# M8340X2.net
KiCad netlist of a schematic drawn in EAGLE
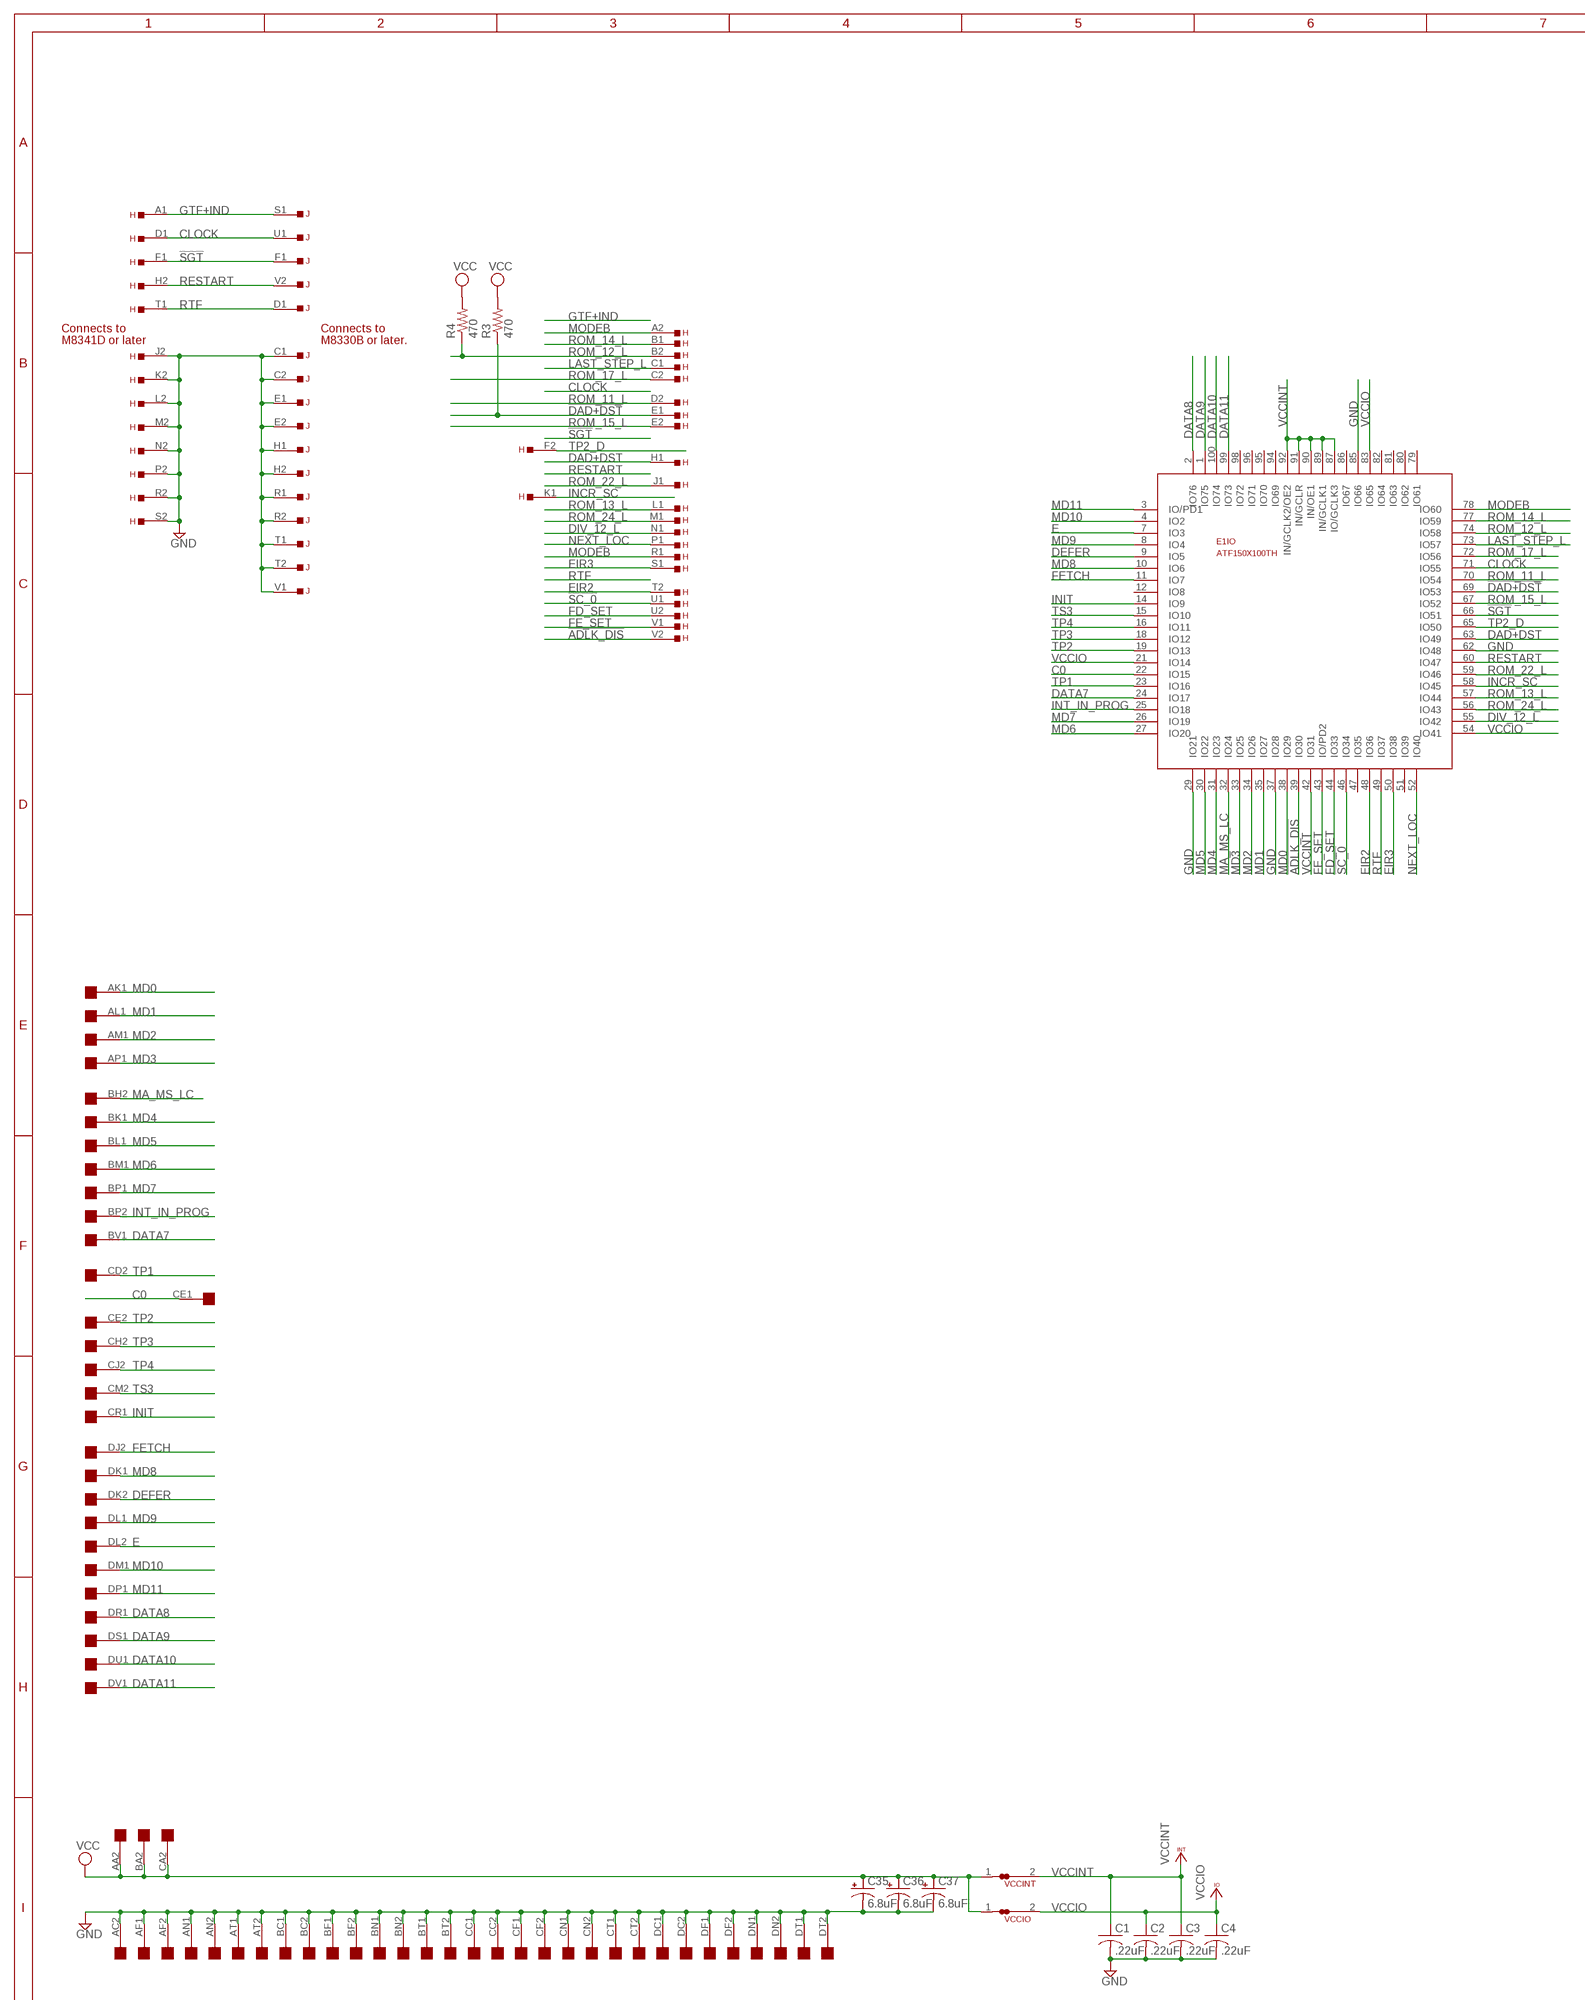
[diagram p0: schematic, sheet 1, part 1 of 2]
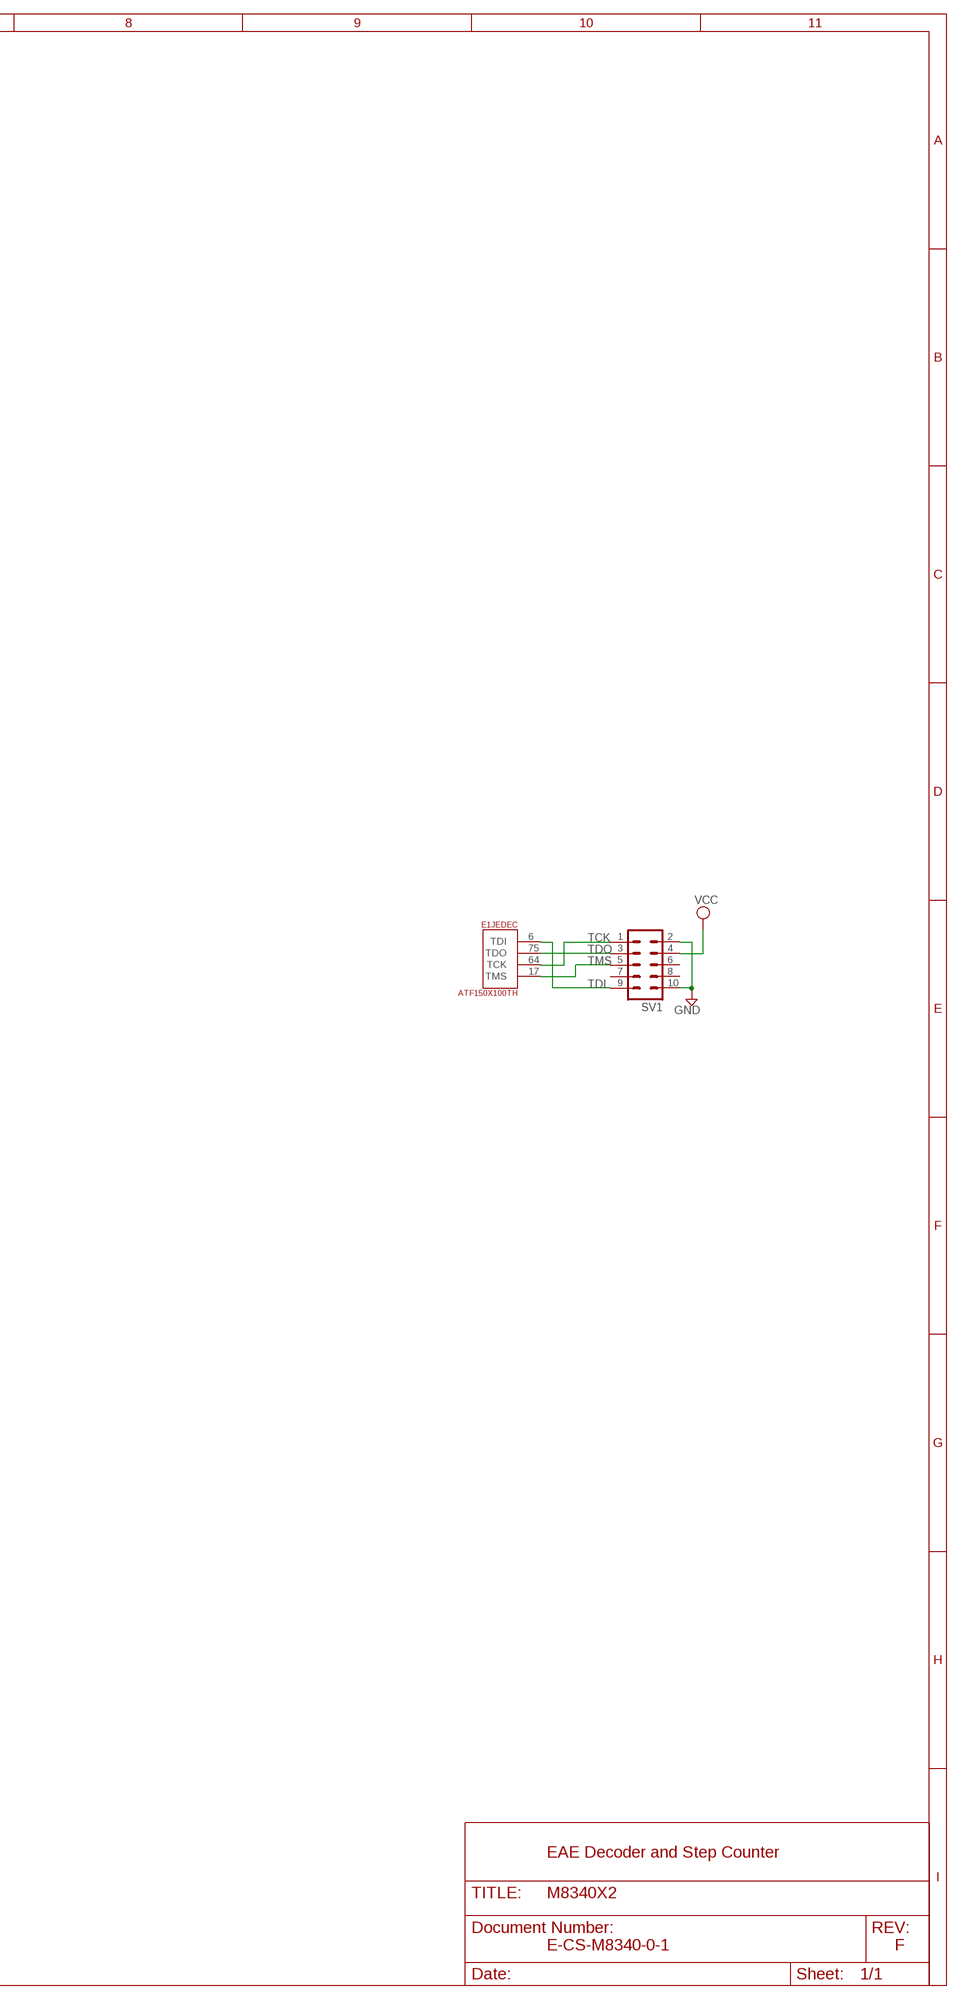
[diagram p1: schematic, sheet 1, part 2 of 2]

(export (version "E")
  (design (tool "Eeschema 10.0.6"))
  (components
    (comp (ref "C1")
      (value ".22uF")
      (footprint "eagle-import:C063-025X075")
      (libsource (lib "eagle-import") (part "C-US"))
    )
    (comp (ref "C2")
      (value ".22uF")
      (footprint "eagle-import:C063-025X075")
      (libsource (lib "eagle-import") (part "C-US"))
    )
    (comp (ref "C3")
      (value ".22uF")
      (footprint "eagle-import:C063-025X075")
      (libsource (lib "eagle-import") (part "C-US"))
    )
    (comp (ref "C4")
      (value ".22uF")
      (footprint "eagle-import:C063-025X075")
      (libsource (lib "eagle-import") (part "C-US"))
    )
    (comp (ref "C35")
      (value "6.8uF")
      (footprint "eagle-import:E12-8")
      (libsource (lib "eagle-import") (part "CPOL-USE20-8AXIAL"))
    )
    (comp (ref "C36")
      (value "6.8uF")
      (footprint "eagle-import:E12-8")
      (libsource (lib "eagle-import") (part "CPOL-USE20-8AXIAL"))
    )
    (comp (ref "C37")
      (value "6.8uF")
      (footprint "eagle-import:E12-8")
      (libsource (lib "eagle-import") (part "CPOL-USE20-8AXIAL"))
    )
    (comp (ref "E1")
      (value "ATF150X100TH")
      (footprint "eagle-import:TH-100")
      (libsource (lib "eagle-import") (part "ATF150X100TH"))
    )
    (comp (ref "H")
      (value "EDGE-TOP")
      (footprint "eagle-import:EDGE-CON2")
      (libsource (lib "eagle-import") (part "EDGE-TOP"))
    )
    (comp (ref "J")
      (value "EDGE-TOP")
      (footprint "eagle-import:EDGE-CON2")
      (libsource (lib "eagle-import") (part "EDGE-TOP"))
    )
    (comp (ref "R3")
      (value "470")
      (footprint "eagle-import:0207_10")
      (libsource (lib "eagle-import") (part "R-US_0207/10"))
    )
    (comp (ref "R4")
      (value "470")
      (footprint "eagle-import:0207_10")
      (libsource (lib "eagle-import") (part "R-US_0207/10"))
    )
    (comp (ref "SV1")
      (value "ML10")
      (footprint "eagle-import:ML10")
      (libsource (lib "eagle-import") (part "ML10"))
    )
    (comp (ref "U$1")
      (value "QUAD")
      (footprint "eagle-import:EDGE-CON8")
      (libsource (lib "eagle-import") (part "QUAD"))
    )
    (comp (ref "VCCINT")
      (value "JUMPER-NC1")
      (footprint "eagle-import:NC1")
      (libsource (lib "eagle-import") (part "JUMPER-NC1"))
    )
    (comp (ref "VCCIO")
      (value "JUMPER-NC1")
      (footprint "eagle-import:NC1")
      (libsource (lib "eagle-import") (part "JUMPER-NC1"))
    )
  )
  (nets
    (net (code "1") (name "/C0") (class "Default")
      (node (ref "E1") (pin "22") (pinfunction "IO15_22") (pintype "bidirectional"))
      (node (ref "U$1") (pin "CE1") (pinfunction "1_CE1") (pintype "bidirectional"))
    )
    (net (code "2") (name "/CLOCK") (class "Default")
      (node (ref "E1") (pin "71") (pinfunction "IO55_71") (pintype "bidirectional"))
      (node (ref "H") (pin "D1") (pinfunction "P_D1") (pintype "passive"))
      (node (ref "J") (pin "U1") (pinfunction "P_U1") (pintype "passive"))
    )
    (net (code "3") (name "/DAD+DST") (class "Default")
      (node (ref "E1") (pin "63") (pinfunction "IO49_63") (pintype "bidirectional"))
      (node (ref "H") (pin "H1") (pinfunction "P_H1") (pintype "passive"))
    )
    (net (code "4") (name "/DATA7") (class "Default")
      (node (ref "E1") (pin "24") (pinfunction "IO17_24") (pintype "bidirectional"))
      (node (ref "U$1") (pin "BV1") (pinfunction "1_BV1") (pintype "bidirectional"))
    )
    (net (code "5") (name "/DATA8") (class "Default")
      (node (ref "E1") (pin "2") (pinfunction "IO76_2") (pintype "bidirectional"))
      (node (ref "U$1") (pin "DR1") (pinfunction "1_DR1") (pintype "bidirectional"))
    )
    (net (code "6") (name "/DATA9") (class "Default")
      (node (ref "E1") (pin "1") (pinfunction "IO75_1") (pintype "bidirectional"))
      (node (ref "U$1") (pin "DS1") (pinfunction "1_DS1") (pintype "bidirectional"))
    )
    (net (code "7") (name "/DATA10") (class "Default")
      (node (ref "E1") (pin "100") (pinfunction "IO74_100") (pintype "bidirectional"))
      (node (ref "U$1") (pin "DU1") (pinfunction "1_DU1") (pintype "bidirectional"))
    )
    (net (code "8") (name "/DATA11") (class "Default")
      (node (ref "E1") (pin "99") (pinfunction "IO73_99") (pintype "bidirectional"))
      (node (ref "U$1") (pin "DV1") (pinfunction "1_DV1") (pintype "bidirectional"))
    )
    (net (code "9") (name "/DEFER") (class "Default")
      (node (ref "E1") (pin "9") (pinfunction "IO5_9") (pintype "bidirectional"))
      (node (ref "U$1") (pin "DK2") (pinfunction "1_DK2") (pintype "bidirectional"))
    )
    (net (code "10") (name "/DIV_12_L") (class "Default")
      (node (ref "E1") (pin "55") (pinfunction "IO42_55") (pintype "bidirectional"))
      (node (ref "H") (pin "N1") (pinfunction "P_N1") (pintype "passive"))
    )
    (net (code "11") (name "/E") (class "Default")
      (node (ref "E1") (pin "7") (pinfunction "IO3_7") (pintype "bidirectional"))
      (node (ref "U$1") (pin "DL2") (pinfunction "1_DL2") (pintype "bidirectional"))
    )
    (net (code "12") (name "/EIR2") (class "Default")
      (node (ref "E1") (pin "48") (pinfunction "IO36_48") (pintype "bidirectional"))
      (node (ref "H") (pin "T2") (pinfunction "P_T2") (pintype "passive"))
    )
    (net (code "13") (name "/EIR3") (class "Default")
      (node (ref "E1") (pin "50") (pinfunction "IO38_50") (pintype "bidirectional"))
      (node (ref "H") (pin "S1") (pinfunction "P_S1") (pintype "passive"))
    )
    (net (code "14") (name "/FD_SET") (class "Default")
      (node (ref "E1") (pin "44") (pinfunction "IO33_44") (pintype "bidirectional"))
      (node (ref "H") (pin "U2") (pinfunction "P_U2") (pintype "passive"))
    )
    (net (code "15") (name "/FETCH") (class "Default")
      (node (ref "E1") (pin "11") (pinfunction "IO7_11") (pintype "bidirectional"))
      (node (ref "U$1") (pin "DJ2") (pinfunction "1_DJ2") (pintype "bidirectional"))
    )
    (net (code "16") (name "/FE_SET") (class "Default")
      (node (ref "E1") (pin "43") (pinfunction "IO/PD2_43") (pintype "bidirectional"))
      (node (ref "H") (pin "V1") (pinfunction "P_V1") (pintype "passive"))
    )
    (net (code "17") (name "/GTF+IND") (class "Default")
      (node (ref "H") (pin "A1") (pinfunction "P_A1") (pintype "passive"))
      (node (ref "J") (pin "S1") (pinfunction "P_S1") (pintype "passive"))
    )
    (net (code "18") (name "/INCR_SC") (class "Default")
      (node (ref "E1") (pin "58") (pinfunction "IO45_58") (pintype "bidirectional"))
      (node (ref "H") (pin "K1") (pinfunction "P_K1") (pintype "passive"))
    )
    (net (code "19") (name "/INIT") (class "Default")
      (node (ref "E1") (pin "14") (pinfunction "IO9_14") (pintype "bidirectional"))
      (node (ref "U$1") (pin "CR1") (pinfunction "1_CR1") (pintype "bidirectional"))
    )
    (net (code "20") (name "/INT_IN_PROG") (class "Default")
      (node (ref "E1") (pin "25") (pinfunction "IO18_25") (pintype "bidirectional"))
      (node (ref "U$1") (pin "BP2") (pinfunction "1_BP2") (pintype "bidirectional"))
    )
    (net (code "21") (name "/LAST_STEP_L") (class "Default")
      (node (ref "E1") (pin "73") (pinfunction "IO57_73") (pintype "bidirectional"))
      (node (ref "H") (pin "C1") (pinfunction "P_C1") (pintype "passive"))
    )
    (net (code "22") (name "/MA_MS_LC") (class "Default")
      (node (ref "E1") (pin "32") (pinfunction "IO24_32") (pintype "bidirectional"))
      (node (ref "U$1") (pin "BH2") (pinfunction "1_BH2") (pintype "bidirectional"))
    )
    (net (code "23") (name "/MD0") (class "Default")
      (node (ref "E1") (pin "38") (pinfunction "IO29_38") (pintype "bidirectional"))
      (node (ref "U$1") (pin "AK1") (pinfunction "1_AK1") (pintype "bidirectional"))
    )
    (net (code "24") (name "/MD1") (class "Default")
      (node (ref "E1") (pin "35") (pinfunction "IO27_35") (pintype "bidirectional"))
      (node (ref "U$1") (pin "AL1") (pinfunction "1_AL1") (pintype "bidirectional"))
    )
    (net (code "25") (name "/MD2") (class "Default")
      (node (ref "E1") (pin "34") (pinfunction "IO26_34") (pintype "bidirectional"))
      (node (ref "U$1") (pin "AM1") (pinfunction "1_AM1") (pintype "bidirectional"))
    )
    (net (code "26") (name "/MD3") (class "Default")
      (node (ref "E1") (pin "33") (pinfunction "IO25_33") (pintype "bidirectional"))
      (node (ref "U$1") (pin "AP1") (pinfunction "1_AP1") (pintype "bidirectional"))
    )
    (net (code "27") (name "/MD4") (class "Default")
      (node (ref "E1") (pin "31") (pinfunction "IO23_31") (pintype "bidirectional"))
      (node (ref "U$1") (pin "BK1") (pinfunction "1_BK1") (pintype "bidirectional"))
    )
    (net (code "28") (name "/MD5") (class "Default")
      (node (ref "E1") (pin "30") (pinfunction "IO22_30") (pintype "bidirectional"))
      (node (ref "U$1") (pin "BL1") (pinfunction "1_BL1") (pintype "bidirectional"))
    )
    (net (code "29") (name "/MD6") (class "Default")
      (node (ref "E1") (pin "27") (pinfunction "IO20_27") (pintype "bidirectional"))
      (node (ref "U$1") (pin "BM1") (pinfunction "1_BM1") (pintype "bidirectional"))
    )
    (net (code "30") (name "/MD7") (class "Default")
      (node (ref "E1") (pin "26") (pinfunction "IO19_26") (pintype "bidirectional"))
      (node (ref "U$1") (pin "BP1") (pinfunction "1_BP1") (pintype "bidirectional"))
    )
    (net (code "31") (name "/MD8") (class "Default")
      (node (ref "E1") (pin "10") (pinfunction "IO6_10") (pintype "bidirectional"))
      (node (ref "U$1") (pin "DK1") (pinfunction "1_DK1") (pintype "bidirectional"))
    )
    (net (code "32") (name "/MD9") (class "Default")
      (node (ref "E1") (pin "8") (pinfunction "IO4_8") (pintype "bidirectional"))
      (node (ref "U$1") (pin "DL1") (pinfunction "1_DL1") (pintype "bidirectional"))
    )
    (net (code "33") (name "/MD10") (class "Default")
      (node (ref "E1") (pin "4") (pinfunction "IO2_4") (pintype "bidirectional"))
      (node (ref "U$1") (pin "DM1") (pinfunction "1_DM1") (pintype "bidirectional"))
    )
    (net (code "34") (name "/MD11") (class "Default")
      (node (ref "E1") (pin "3") (pinfunction "IO/PD1_3") (pintype "bidirectional"))
      (node (ref "U$1") (pin "DP1") (pinfunction "1_DP1") (pintype "bidirectional"))
    )
    (net (code "35") (name "/MODEB") (class "Default")
      (node (ref "E1") (pin "78") (pinfunction "IO60_78") (pintype "bidirectional"))
      (node (ref "H") (pin "A2") (pinfunction "P_A2") (pintype "passive"))
      (node (ref "H") (pin "R1") (pinfunction "P_R1") (pintype "passive"))
    )
    (net (code "36") (name "/NEXT_LOC") (class "Default")
      (node (ref "E1") (pin "52") (pinfunction "IO40_52") (pintype "bidirectional"))
      (node (ref "H") (pin "P1") (pinfunction "P_P1") (pintype "passive"))
    )
    (net (code "37") (name "/RESTART") (class "Default")
      (node (ref "E1") (pin "60") (pinfunction "IO47_60") (pintype "bidirectional"))
      (node (ref "H") (pin "H2") (pinfunction "P_H2") (pintype "passive"))
      (node (ref "J") (pin "V2") (pinfunction "P_V2") (pintype "passive"))
    )
    (net (code "38") (name "/ROM_11_L") (class "Default")
      (node (ref "E1") (pin "70") (pinfunction "IO54_70") (pintype "bidirectional"))
      (node (ref "H") (pin "D2") (pinfunction "P_D2") (pintype "passive"))
    )
    (net (code "39") (name "/ROM_12_L") (class "Default")
      (node (ref "E1") (pin "74") (pinfunction "IO58_74") (pintype "bidirectional"))
      (node (ref "H") (pin "B2") (pinfunction "P_B2") (pintype "passive"))
      (node (ref "R4") (pin "1") (pinfunction "1_1") (pintype "passive"))
    )
    (net (code "40") (name "/ROM_13_L") (class "Default")
      (node (ref "E1") (pin "57") (pinfunction "IO44_57") (pintype "bidirectional"))
      (node (ref "H") (pin "L1") (pinfunction "P_L1") (pintype "passive"))
    )
    (net (code "41") (name "/ROM_14_L") (class "Default")
      (node (ref "E1") (pin "77") (pinfunction "IO59_77") (pintype "bidirectional"))
      (node (ref "H") (pin "B1") (pinfunction "P_B1") (pintype "passive"))
    )
    (net (code "42") (name "/ROM_15_L") (class "Default")
      (node (ref "E1") (pin "67") (pinfunction "IO52_67") (pintype "bidirectional"))
      (node (ref "H") (pin "E2") (pinfunction "P_E2") (pintype "passive"))
    )
    (net (code "43") (name "/ROM_17_L") (class "Default")
      (node (ref "E1") (pin "72") (pinfunction "IO56_72") (pintype "bidirectional"))
      (node (ref "H") (pin "C2") (pinfunction "P_C2") (pintype "passive"))
    )
    (net (code "44") (name "/ROM_22_L") (class "Default")
      (node (ref "E1") (pin "59") (pinfunction "IO46_59") (pintype "bidirectional"))
      (node (ref "H") (pin "J1") (pinfunction "P_J1") (pintype "passive"))
    )
    (net (code "45") (name "/ROM_24_L") (class "Default")
      (node (ref "E1") (pin "56") (pinfunction "IO43_56") (pintype "bidirectional"))
      (node (ref "H") (pin "M1") (pinfunction "P_M1") (pintype "passive"))
    )
    (net (code "46") (name "/RTF") (class "Default")
      (node (ref "E1") (pin "49") (pinfunction "IO37_49") (pintype "bidirectional"))
      (node (ref "H") (pin "T1") (pinfunction "P_T1") (pintype "passive"))
      (node (ref "J") (pin "D1") (pinfunction "P_D1") (pintype "passive"))
    )
    (net (code "47") (name "/TCK") (class "Default")
      (node (ref "E1") (pin "64") (pinfunction "TCK_64") (pintype "bidirectional"))
      (node (ref "SV1") (pin "1") (pinfunction "1_1") (pintype "passive"))
    )
    (net (code "48") (name "/TDI") (class "Default")
      (node (ref "E1") (pin "6") (pinfunction "TDI_6") (pintype "bidirectional"))
      (node (ref "SV1") (pin "9") (pinfunction "9_9") (pintype "passive"))
    )
    (net (code "49") (name "/TDO") (class "Default")
      (node (ref "E1") (pin "75") (pinfunction "TDO_75") (pintype "bidirectional"))
      (node (ref "SV1") (pin "3") (pinfunction "3_3") (pintype "passive"))
    )
    (net (code "50") (name "/TMS") (class "Default")
      (node (ref "E1") (pin "17") (pinfunction "TMS_17") (pintype "bidirectional"))
      (node (ref "SV1") (pin "5") (pinfunction "5_5") (pintype "passive"))
    )
    (net (code "51") (name "/TP1") (class "Default")
      (node (ref "E1") (pin "23") (pinfunction "IO16_23") (pintype "bidirectional"))
      (node (ref "U$1") (pin "CD2") (pinfunction "1_CD2") (pintype "bidirectional"))
    )
    (net (code "52") (name "/TP2") (class "Default")
      (node (ref "E1") (pin "19") (pinfunction "IO13_19") (pintype "bidirectional"))
      (node (ref "U$1") (pin "CE2") (pinfunction "1_CE2") (pintype "bidirectional"))
    )
    (net (code "53") (name "/TP2_D") (class "Default")
      (node (ref "E1") (pin "65") (pinfunction "IO50_65") (pintype "bidirectional"))
      (node (ref "H") (pin "F2") (pinfunction "P_F2") (pintype "passive"))
    )
    (net (code "54") (name "/TP3") (class "Default")
      (node (ref "E1") (pin "18") (pinfunction "IO12_18") (pintype "bidirectional"))
      (node (ref "U$1") (pin "CH2") (pinfunction "1_CH2") (pintype "bidirectional"))
    )
    (net (code "55") (name "/TP4") (class "Default")
      (node (ref "E1") (pin "16") (pinfunction "IO11_16") (pintype "bidirectional"))
      (node (ref "U$1") (pin "CJ2") (pinfunction "1_CJ2") (pintype "bidirectional"))
    )
    (net (code "56") (name "/TS3") (class "Default")
      (node (ref "E1") (pin "15") (pinfunction "IO10_15") (pintype "bidirectional"))
      (node (ref "U$1") (pin "CM2") (pinfunction "1_CM2") (pintype "bidirectional"))
    )
    (net (code "57") (name "/~{ADLK_DIS}") (class "Default")
      (node (ref "E1") (pin "39") (pinfunction "IO30_39") (pintype "bidirectional"))
      (node (ref "H") (pin "V2") (pinfunction "P_V2") (pintype "passive"))
    )
    (net (code "58") (name "/~{DAD+DST}") (class "Default")
      (node (ref "E1") (pin "69") (pinfunction "IO53_69") (pintype "bidirectional"))
      (node (ref "H") (pin "E1") (pinfunction "P_E1") (pintype "passive"))
      (node (ref "R3") (pin "1") (pinfunction "1_1") (pintype "passive"))
    )
    (net (code "59") (name "/~{SC_0}") (class "Default")
      (node (ref "E1") (pin "46") (pinfunction "IO34_46") (pintype "bidirectional"))
      (node (ref "H") (pin "U1") (pinfunction "P_U1") (pintype "passive"))
    )
    (net (code "60") (name "/~{SGT}") (class "Default")
      (node (ref "E1") (pin "66") (pinfunction "IO51_66") (pintype "bidirectional"))
      (node (ref "H") (pin "F1") (pinfunction "P_F1") (pintype "passive"))
      (node (ref "J") (pin "F1") (pinfunction "P_F1") (pintype "passive"))
    )
    (net (code "61") (name "GND") (class "Default")
      (node (ref "C1") (pin "2") (pinfunction "2_2") (pintype "passive"))
      (node (ref "C2") (pin "2") (pinfunction "2_2") (pintype "passive"))
      (node (ref "C3") (pin "2") (pinfunction "2_2") (pintype "passive"))
      (node (ref "C35") (pin "-") (pinfunction "-_-") (pintype "passive"))
      (node (ref "C36") (pin "-") (pinfunction "-_-") (pintype "passive"))
      (node (ref "C37") (pin "-") (pinfunction "-_-") (pintype "passive"))
      (node (ref "C4") (pin "2") (pinfunction "2_2") (pintype "passive"))
      (node (ref "E1") (pin "29") (pinfunction "IO21_29") (pintype "bidirectional"))
      (node (ref "E1") (pin "37") (pinfunction "IO28_37") (pintype "bidirectional"))
      (node (ref "E1") (pin "62") (pinfunction "IO48_62") (pintype "bidirectional"))
      (node (ref "E1") (pin "85") (pinfunction "IO66_85") (pintype "bidirectional"))
      (node (ref "H") (pin "J2") (pinfunction "P_J2") (pintype "passive"))
      (node (ref "H") (pin "K2") (pinfunction "P_K2") (pintype "passive"))
      (node (ref "H") (pin "L2") (pinfunction "P_L2") (pintype "passive"))
      (node (ref "H") (pin "M2") (pinfunction "P_M2") (pintype "passive"))
      (node (ref "H") (pin "N2") (pinfunction "P_N2") (pintype "passive"))
      (node (ref "H") (pin "P2") (pinfunction "P_P2") (pintype "passive"))
      (node (ref "H") (pin "R2") (pinfunction "P_R2") (pintype "passive"))
      (node (ref "H") (pin "S2") (pinfunction "P_S2") (pintype "passive"))
      (node (ref "J") (pin "C1") (pinfunction "P_C1") (pintype "passive"))
      (node (ref "J") (pin "C2") (pinfunction "P_C2") (pintype "passive"))
      (node (ref "J") (pin "E1") (pinfunction "P_E1") (pintype "passive"))
      (node (ref "J") (pin "E2") (pinfunction "P_E2") (pintype "passive"))
      (node (ref "J") (pin "H1") (pinfunction "P_H1") (pintype "passive"))
      (node (ref "J") (pin "H2") (pinfunction "P_H2") (pintype "passive"))
      (node (ref "J") (pin "R1") (pinfunction "P_R1") (pintype "passive"))
      (node (ref "J") (pin "R2") (pinfunction "P_R2") (pintype "passive"))
      (node (ref "J") (pin "T1") (pinfunction "P_T1") (pintype "passive"))
      (node (ref "J") (pin "T2") (pinfunction "P_T2") (pintype "passive"))
      (node (ref "J") (pin "V1") (pinfunction "P_V1") (pintype "passive"))
      (node (ref "SV1") (pin "10") (pinfunction "10_10") (pintype "passive"))
      (node (ref "SV1") (pin "2") (pinfunction "2_2") (pintype "passive"))
      (node (ref "U$1") (pin "AC2") (pinfunction "1_AC2") (pintype "bidirectional"))
      (node (ref "U$1") (pin "AF1") (pinfunction "1_AF1") (pintype "bidirectional"))
      (node (ref "U$1") (pin "AF2") (pinfunction "1_AF2") (pintype "bidirectional"))
      (node (ref "U$1") (pin "AN1") (pinfunction "1_AN1") (pintype "bidirectional"))
      (node (ref "U$1") (pin "AN2") (pinfunction "1_AN2") (pintype "bidirectional"))
      (node (ref "U$1") (pin "AT1") (pinfunction "1_AT1") (pintype "bidirectional"))
      (node (ref "U$1") (pin "AT2") (pinfunction "1_AT2") (pintype "bidirectional"))
      (node (ref "U$1") (pin "BC1") (pinfunction "1_BC1") (pintype "bidirectional"))
      (node (ref "U$1") (pin "BC2") (pinfunction "1_BC2") (pintype "bidirectional"))
      (node (ref "U$1") (pin "BF1") (pinfunction "1_BF1") (pintype "bidirectional"))
      (node (ref "U$1") (pin "BF2") (pinfunction "1_BF2") (pintype "bidirectional"))
      (node (ref "U$1") (pin "BN1") (pinfunction "1_BN1") (pintype "bidirectional"))
      (node (ref "U$1") (pin "BN2") (pinfunction "1_BN2") (pintype "bidirectional"))
      (node (ref "U$1") (pin "BT1") (pinfunction "1_BT1") (pintype "bidirectional"))
      (node (ref "U$1") (pin "BT2") (pinfunction "1_BT2") (pintype "bidirectional"))
      (node (ref "U$1") (pin "CC1") (pinfunction "1_CC1") (pintype "bidirectional"))
      (node (ref "U$1") (pin "CC2") (pinfunction "1_CC2") (pintype "bidirectional"))
      (node (ref "U$1") (pin "CF1") (pinfunction "1_CF1") (pintype "bidirectional"))
      (node (ref "U$1") (pin "CF2") (pinfunction "1_CF2") (pintype "bidirectional"))
      (node (ref "U$1") (pin "CN1") (pinfunction "1_CN1") (pintype "bidirectional"))
      (node (ref "U$1") (pin "CN2") (pinfunction "1_CN2") (pintype "bidirectional"))
      (node (ref "U$1") (pin "CT1") (pinfunction "1_CT1") (pintype "bidirectional"))
      (node (ref "U$1") (pin "CT2") (pinfunction "1_CT2") (pintype "bidirectional"))
      (node (ref "U$1") (pin "DC1") (pinfunction "1_DC1") (pintype "bidirectional"))
      (node (ref "U$1") (pin "DC2") (pinfunction "1_DC2") (pintype "bidirectional"))
      (node (ref "U$1") (pin "DF1") (pinfunction "1_DF1") (pintype "bidirectional"))
      (node (ref "U$1") (pin "DF2") (pinfunction "1_DF2") (pintype "bidirectional"))
      (node (ref "U$1") (pin "DN1") (pinfunction "1_DN1") (pintype "bidirectional"))
      (node (ref "U$1") (pin "DN2") (pinfunction "1_DN2") (pintype "bidirectional"))
      (node (ref "U$1") (pin "DT1") (pinfunction "1_DT1") (pintype "bidirectional"))
      (node (ref "U$1") (pin "DT2") (pinfunction "1_DT2") (pintype "bidirectional"))
    )
    (net (code "62") (name "VCC") (class "Default")
      (node (ref "C35") (pin "+") (pinfunction "+_+") (pintype "passive"))
      (node (ref "C36") (pin "+") (pinfunction "+_+") (pintype "passive"))
      (node (ref "C37") (pin "+") (pinfunction "+_+") (pintype "passive"))
      (node (ref "R3") (pin "2") (pinfunction "2_2") (pintype "passive"))
      (node (ref "R4") (pin "2") (pinfunction "2_2") (pintype "passive"))
      (node (ref "SV1") (pin "4") (pinfunction "4_4") (pintype "passive"))
      (node (ref "U$1") (pin "AA2") (pinfunction "1_AA2") (pintype "bidirectional"))
      (node (ref "U$1") (pin "BA2") (pinfunction "1_BA2") (pintype "bidirectional"))
      (node (ref "U$1") (pin "CA2") (pinfunction "1_CA2") (pintype "bidirectional"))
      (node (ref "VCCINT") (pin "1") (pinfunction "1_1") (pintype "bidirectional"))
      (node (ref "VCCIO") (pin "1") (pinfunction "1_1") (pintype "bidirectional"))
    )
    (net (code "63") (name "VCCINT") (class "Default")
      (node (ref "C1") (pin "1") (pinfunction "1_1") (pintype "passive"))
      (node (ref "C3") (pin "1") (pinfunction "1_1") (pintype "passive"))
      (node (ref "E1") (pin "42") (pinfunction "IO31_42") (pintype "bidirectional"))
      (node (ref "E1") (pin "87") (pinfunction "IO/GCLK3_87") (pintype "bidirectional"))
      (node (ref "E1") (pin "89") (pinfunction "IN/GCLK1_89") (pintype "input"))
      (node (ref "E1") (pin "90") (pinfunction "IN/OE1_90") (pintype "input"))
      (node (ref "E1") (pin "91") (pinfunction "IN/GCLR_91") (pintype "input"))
      (node (ref "E1") (pin "92") (pinfunction "IN/GCLK2/OE2_92") (pintype "input"))
      (node (ref "VCCINT") (pin "2") (pinfunction "2_2") (pintype "bidirectional"))
    )
    (net (code "64") (name "VCCIO") (class "Default")
      (node (ref "C2") (pin "1") (pinfunction "1_1") (pintype "passive"))
      (node (ref "C4") (pin "1") (pinfunction "1_1") (pintype "passive"))
      (node (ref "E1") (pin "21") (pinfunction "IO14_21") (pintype "bidirectional"))
      (node (ref "E1") (pin "54") (pinfunction "IO41_54") (pintype "bidirectional"))
      (node (ref "E1") (pin "83") (pinfunction "IO65_83") (pintype "bidirectional"))
      (node (ref "VCCIO") (pin "2") (pinfunction "2_2") (pintype "bidirectional"))
    )
    (net (code "65") (name "unconnected-(E1Q-IO8-Pad12)") (class "Default")
      (node (ref "E1") (pin "12") (pinfunction "IO8_12") (pintype "bidirectional"))
    )
    (net (code "66") (name "unconnected-(E1Q-IO35-Pad47)") (class "Default")
      (node (ref "E1") (pin "47") (pinfunction "IO35_47") (pintype "bidirectional"))
    )
    (net (code "67") (name "unconnected-(E1Q-IO39-Pad51)") (class "Default")
      (node (ref "E1") (pin "51") (pinfunction "IO39_51") (pintype "bidirectional"))
    )
    (net (code "68") (name "unconnected-(E1Q-IO61-Pad79)") (class "Default")
      (node (ref "E1") (pin "79") (pinfunction "IO61_79") (pintype "bidirectional"))
    )
    (net (code "69") (name "unconnected-(E1Q-IO62-Pad80)") (class "Default")
      (node (ref "E1") (pin "80") (pinfunction "IO62_80") (pintype "bidirectional"))
    )
    (net (code "70") (name "unconnected-(E1Q-IO63-Pad81)") (class "Default")
      (node (ref "E1") (pin "81") (pinfunction "IO63_81") (pintype "bidirectional"))
    )
    (net (code "71") (name "unconnected-(E1Q-IO64-Pad82)") (class "Default")
      (node (ref "E1") (pin "82") (pinfunction "IO64_82") (pintype "bidirectional"))
    )
    (net (code "72") (name "unconnected-(E1Q-IO67-Pad86)") (class "Default")
      (node (ref "E1") (pin "86") (pinfunction "IO67_86") (pintype "bidirectional"))
    )
    (net (code "73") (name "unconnected-(E1Q-IO69-Pad94)") (class "Default")
      (node (ref "E1") (pin "94") (pinfunction "IO69_94") (pintype "bidirectional"))
    )
    (net (code "74") (name "unconnected-(E1Q-IO70-Pad95)") (class "Default")
      (node (ref "E1") (pin "95") (pinfunction "IO70_95") (pintype "bidirectional"))
    )
    (net (code "75") (name "unconnected-(E1Q-IO71-Pad96)") (class "Default")
      (node (ref "E1") (pin "96") (pinfunction "IO71_96") (pintype "bidirectional"))
    )
    (net (code "76") (name "unconnected-(E1Q-IO72-Pad98)") (class "Default")
      (node (ref "E1") (pin "98") (pinfunction "IO72_98") (pintype "bidirectional"))
    )
    (net (code "77") (name "unconnected-(SV1-Pad6)") (class "Default")
      (node (ref "SV1") (pin "6") (pinfunction "6_6") (pintype "passive"))
    )
    (net (code "78") (name "unconnected-(SV1-Pad7)") (class "Default")
      (node (ref "SV1") (pin "7") (pinfunction "7_7") (pintype "passive"))
    )
    (net (code "79") (name "unconnected-(SV1-Pad8)") (class "Default")
      (node (ref "SV1") (pin "8") (pinfunction "8_8") (pintype "passive"))
    )
  )
)
